# LedKeychain.net
KiCad netlist of a schematic drawn in EAGLE
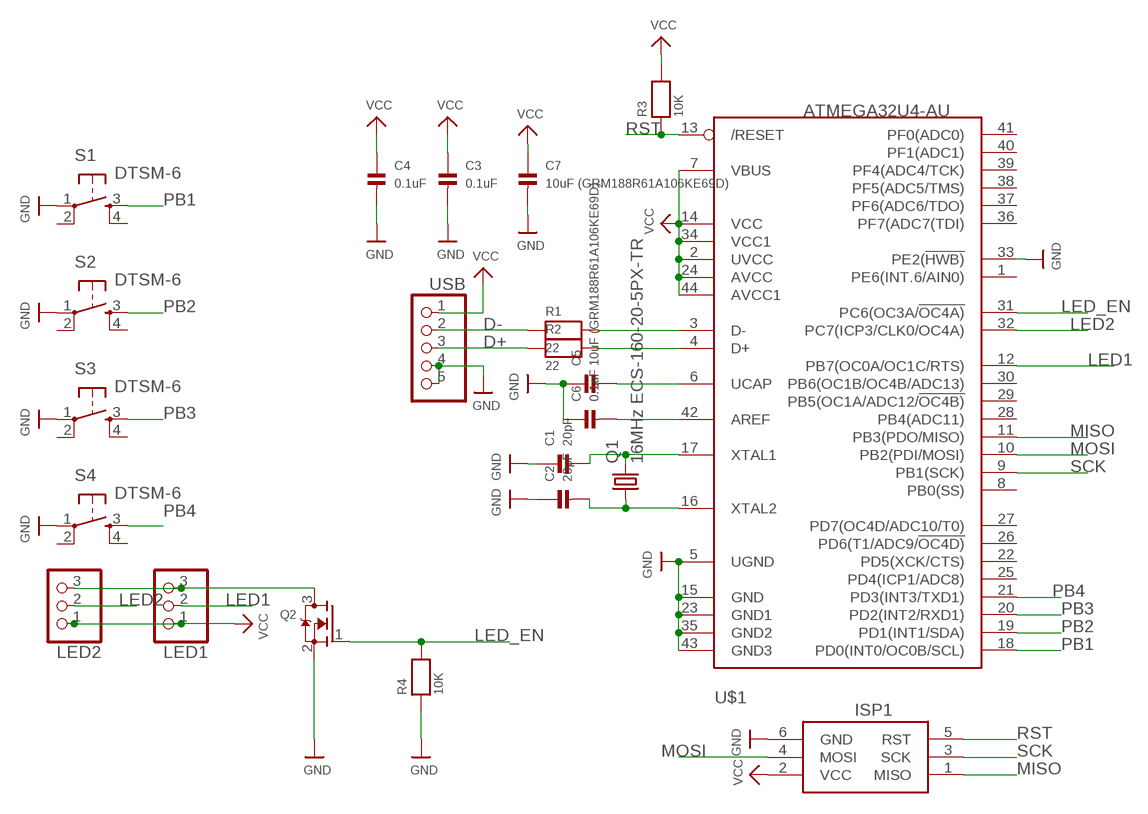
[diagram p0: schematic, sheet 1]

(export (version "E")
  (design (tool "Eeschema 10.0.6"))
  (components
    (comp (ref "C1")
      (value "20pF")
      (footprint "eagle-import:0603-MINI")
      (libsource (lib "eagle-import") (part "CAP_CERAMIC0603MINI"))
    )
    (comp (ref "C2")
      (value "20pF")
      (footprint "eagle-import:0603-MINI")
      (libsource (lib "eagle-import") (part "CAP_CERAMIC0603MINI"))
    )
    (comp (ref "C3")
      (value "0.1uF")
      (footprint "eagle-import:0603-MINI")
      (libsource (lib "eagle-import") (part "CAP_CERAMIC0603MINI"))
    )
    (comp (ref "C4")
      (value "0.1uF")
      (footprint "eagle-import:0603-MINI")
      (libsource (lib "eagle-import") (part "CAP_CERAMIC0603MINI"))
    )
    (comp (ref "C5")
      (value "10uF (GRM188R61A106KE69D)")
      (footprint "eagle-import:0603-MINI")
      (libsource (lib "eagle-import") (part "CAP_CERAMIC0603MINI"))
    )
    (comp (ref "C6")
      (value "0.1uF")
      (footprint "eagle-import:0603-MINI")
      (libsource (lib "eagle-import") (part "CAP_CERAMIC0603MINI"))
    )
    (comp (ref "C7")
      (value "10uF (GRM188R61A106KE69D)")
      (footprint "eagle-import:0603-MINI")
      (libsource (lib "eagle-import") (part "CAP_CERAMIC0603MINI"))
    )
    (comp (ref "ISP1")
      (value "AVRISP-6")
      (footprint "eagle-import:AVRISP")
      (libsource (lib "eagle-import") (part "AVRISP-6"))
    )
    (comp (ref "LED1")
      (value "PINHD-1X3")
      (footprint "eagle-import:1X03")
      (libsource (lib "eagle-import") (part "PINHD-1X3"))
    )
    (comp (ref "LED2")
      (value "PINHD-1X3")
      (footprint "eagle-import:1X03")
      (libsource (lib "eagle-import") (part "PINHD-1X3"))
    )
    (comp (ref "Q1")
      (value "16MHz ECS-160-20-5PX-TR")
      (footprint "eagle-import:HC49UP")
      (libsource (lib "eagle-import") (part "CRYSTALHC49UP"))
    )
    (comp (ref "Q2")
      (value "MOSFET-NWIDE")
      (footprint "eagle-import:SOT23-WIDE")
      (libsource (lib "eagle-import") (part "MOSFET-NWIDE"))
    )
    (comp (ref "R1")
      (value "22")
      (footprint "eagle-import:0603-MINI")
      (libsource (lib "eagle-import") (part "RESISTOR0603MINI"))
    )
    (comp (ref "R2")
      (value "22")
      (footprint "eagle-import:0603-MINI")
      (libsource (lib "eagle-import") (part "RESISTOR0603MINI"))
    )
    (comp (ref "R3")
      (value "10K")
      (footprint "eagle-import:0603-MINI")
      (libsource (lib "eagle-import") (part "RESISTOR0603MINI"))
    )
    (comp (ref "R4")
      (value "10K")
      (footprint "eagle-import:0603-MINI")
      (libsource (lib "eagle-import") (part "RESISTOR0603MINI"))
    )
    (comp (ref "S1")
      (value "DTSM-6")
      (footprint "eagle-import:DTSM-6")
      (libsource (lib "eagle-import") (part "DTSM-6"))
    )
    (comp (ref "S2")
      (value "DTSM-6")
      (footprint "eagle-import:DTSM-6")
      (libsource (lib "eagle-import") (part "DTSM-6"))
    )
    (comp (ref "S3")
      (value "DTSM-6")
      (footprint "eagle-import:DTSM-6")
      (libsource (lib "eagle-import") (part "DTSM-6"))
    )
    (comp (ref "S4")
      (value "DTSM-6")
      (footprint "eagle-import:DTSM-6")
      (libsource (lib "eagle-import") (part "DTSM-6"))
    )
    (comp (ref "U$1")
      (value "ATMEGA32U4-AU")
      (footprint "eagle-import:TQFP44")
      (libsource (lib "eagle-import") (part "ATMEGA32U4-AU"))
    )
    (comp (ref "USB")
      (value "PINHD-1X5/90")
      (footprint "eagle-import:1X05_90")
      (libsource (lib "eagle-import") (part "PINHD-1X5/90"))
    )
  )
  (nets
    (net (code "1") (name "/D+") (class "Default")
      (node (ref "R2") (pin "1") (pinfunction "1_1") (pintype "passive"))
      (node (ref "USB") (pin "3") (pinfunction "3_3") (pintype "passive"))
    )
    (net (code "2") (name "/D-") (class "Default")
      (node (ref "R1") (pin "1") (pinfunction "1_1") (pintype "passive"))
      (node (ref "USB") (pin "2") (pinfunction "2_2") (pintype "passive"))
    )
    (net (code "3") (name "/LED1") (class "Default")
      (node (ref "LED1") (pin "2") (pinfunction "2_2") (pintype "passive"))
      (node (ref "U$1") (pin "12") (pinfunction "PB7(OC0A/OC1C/RTS)_12") (pintype "bidirectional"))
    )
    (net (code "4") (name "/LED2") (class "Default")
      (node (ref "LED2") (pin "2") (pinfunction "2_2") (pintype "passive"))
      (node (ref "U$1") (pin "32") (pinfunction "PC7(ICP3/CLK0/OC4A)_32") (pintype "bidirectional"))
    )
    (net (code "5") (name "/LED_EN") (class "Default")
      (node (ref "Q2") (pin "1") (pinfunction "G_1") (pintype "bidirectional"))
      (node (ref "R4") (pin "2") (pinfunction "2_2") (pintype "passive"))
      (node (ref "U$1") (pin "31") (pinfunction "PC6(OC3A/~{OC4A})_31") (pintype "bidirectional"))
    )
    (net (code "6") (name "/MISO") (class "Default")
      (node (ref "ISP1") (pin "1") (pinfunction "MISO_1") (pintype "input"))
      (node (ref "U$1") (pin "11") (pinfunction "PB3(PDO/MISO)_11") (pintype "bidirectional"))
    )
    (net (code "7") (name "/MOSI") (class "Default")
      (node (ref "ISP1") (pin "4") (pinfunction "MOSI_4") (pintype "output"))
      (node (ref "U$1") (pin "10") (pinfunction "PB2(PDI/MOSI)_10") (pintype "bidirectional"))
    )
    (net (code "8") (name "/PB1") (class "Default")
      (node (ref "S1") (pin "3") (pinfunction "3_3") (pintype "passive"))
      (node (ref "U$1") (pin "18") (pinfunction "PD0(INT0/OC0B/SCL)_18") (pintype "bidirectional"))
    )
    (net (code "9") (name "/PB2") (class "Default")
      (node (ref "S2") (pin "3") (pinfunction "3_3") (pintype "passive"))
      (node (ref "U$1") (pin "19") (pinfunction "PD1(INT1/SDA)_19") (pintype "bidirectional"))
    )
    (net (code "10") (name "/PB3") (class "Default")
      (node (ref "S3") (pin "3") (pinfunction "3_3") (pintype "passive"))
      (node (ref "U$1") (pin "20") (pinfunction "PD2(INT2/RXD1)_20") (pintype "bidirectional"))
    )
    (net (code "11") (name "/PB4") (class "Default")
      (node (ref "S4") (pin "3") (pinfunction "3_3") (pintype "passive"))
      (node (ref "U$1") (pin "21") (pinfunction "PD3(INT3/TXD1)_21") (pintype "bidirectional"))
    )
    (net (code "12") (name "/RST") (class "Default")
      (node (ref "ISP1") (pin "5") (pinfunction "RST_5") (pintype "output"))
      (node (ref "R3") (pin "1") (pinfunction "1_1") (pintype "passive"))
      (node (ref "U$1") (pin "13") (pinfunction "/RESET_13") (pintype "bidirectional"))
    )
    (net (code "13") (name "/SCK") (class "Default")
      (node (ref "ISP1") (pin "3") (pinfunction "SCK_3") (pintype "output"))
      (node (ref "U$1") (pin "9") (pinfunction "PB1(SCK)_9") (pintype "bidirectional"))
    )
    (net (code "14") (name "GND") (class "Default")
      (node (ref "C1") (pin "1") (pinfunction "P$1_1") (pintype "passive"))
      (node (ref "C2") (pin "1") (pinfunction "P$1_1") (pintype "passive"))
      (node (ref "C3") (pin "2") (pinfunction "P$2_2") (pintype "passive"))
      (node (ref "C4") (pin "2") (pinfunction "P$2_2") (pintype "passive"))
      (node (ref "C5") (pin "1") (pinfunction "P$1_1") (pintype "passive"))
      (node (ref "C6") (pin "1") (pinfunction "P$1_1") (pintype "passive"))
      (node (ref "C7") (pin "2") (pinfunction "P$2_2") (pintype "passive"))
      (node (ref "ISP1") (pin "6") (pinfunction "GND_6") (pintype "power_in"))
      (node (ref "Q2") (pin "2") (pinfunction "S_2") (pintype "bidirectional"))
      (node (ref "R4") (pin "1") (pinfunction "1_1") (pintype "passive"))
      (node (ref "S1") (pin "1") (pinfunction "1_1") (pintype "passive"))
      (node (ref "S2") (pin "1") (pinfunction "1_1") (pintype "passive"))
      (node (ref "S3") (pin "1") (pinfunction "1_1") (pintype "passive"))
      (node (ref "S4") (pin "1") (pinfunction "1_1") (pintype "passive"))
      (node (ref "U$1") (pin "15") (pinfunction "GND_15") (pintype "bidirectional"))
      (node (ref "U$1") (pin "23") (pinfunction "GND1_23") (pintype "bidirectional"))
      (node (ref "U$1") (pin "33") (pinfunction "PE2(~{HWB})_33") (pintype "bidirectional"))
      (node (ref "U$1") (pin "35") (pinfunction "GND2_35") (pintype "bidirectional"))
      (node (ref "U$1") (pin "43") (pinfunction "GND3_43") (pintype "bidirectional"))
      (node (ref "U$1") (pin "5") (pinfunction "UGND_5") (pintype "bidirectional"))
      (node (ref "USB") (pin "4") (pinfunction "4_4") (pintype "passive"))
      (node (ref "USB") (pin "5") (pinfunction "5_5") (pintype "passive"))
    )
    (net (code "15") (name "Net-(C1-P$2)") (class "Default")
      (node (ref "C1") (pin "2") (pinfunction "P$2_2") (pintype "passive"))
      (node (ref "Q1") (pin "2") (pinfunction "2_2") (pintype "passive"))
      (node (ref "U$1") (pin "17") (pinfunction "XTAL1_17") (pintype "bidirectional"))
    )
    (net (code "16") (name "Net-(C2-P$2)") (class "Default")
      (node (ref "C2") (pin "2") (pinfunction "P$2_2") (pintype "passive"))
      (node (ref "Q1") (pin "1") (pinfunction "1_1") (pintype "passive"))
      (node (ref "U$1") (pin "16") (pinfunction "XTAL2_16") (pintype "bidirectional"))
    )
    (net (code "17") (name "Net-(C5-P$2)") (class "Default")
      (node (ref "C5") (pin "2") (pinfunction "P$2_2") (pintype "passive"))
      (node (ref "U$1") (pin "6") (pinfunction "UCAP_6") (pintype "bidirectional"))
    )
    (net (code "18") (name "Net-(C6-P$2)") (class "Default")
      (node (ref "C6") (pin "2") (pinfunction "P$2_2") (pintype "passive"))
      (node (ref "U$1") (pin "42") (pinfunction "AREF_42") (pintype "bidirectional"))
    )
    (net (code "19") (name "Net-(Q2-D)") (class "Default")
      (node (ref "LED1") (pin "3") (pinfunction "3_3") (pintype "passive"))
      (node (ref "LED2") (pin "3") (pinfunction "3_3") (pintype "passive"))
      (node (ref "Q2") (pin "3") (pinfunction "D_3") (pintype "bidirectional"))
    )
    (net (code "20") (name "Net-(U$1-D+)") (class "Default")
      (node (ref "R2") (pin "2") (pinfunction "2_2") (pintype "passive"))
      (node (ref "U$1") (pin "4") (pinfunction "D+_4") (pintype "bidirectional"))
    )
    (net (code "21") (name "Net-(U$1-D-)") (class "Default")
      (node (ref "R1") (pin "2") (pinfunction "2_2") (pintype "passive"))
      (node (ref "U$1") (pin "3") (pinfunction "D-_3") (pintype "bidirectional"))
    )
    (net (code "22") (name "VCC") (class "Default")
      (node (ref "C3") (pin "1") (pinfunction "P$1_1") (pintype "passive"))
      (node (ref "C4") (pin "1") (pinfunction "P$1_1") (pintype "passive"))
      (node (ref "C7") (pin "1") (pinfunction "P$1_1") (pintype "passive"))
      (node (ref "ISP1") (pin "2") (pinfunction "VCC_2") (pintype "power_in"))
      (node (ref "LED1") (pin "1") (pinfunction "1_1") (pintype "passive"))
      (node (ref "LED2") (pin "1") (pinfunction "1_1") (pintype "passive"))
      (node (ref "R3") (pin "2") (pinfunction "2_2") (pintype "passive"))
      (node (ref "U$1") (pin "14") (pinfunction "VCC_14") (pintype "bidirectional"))
      (node (ref "U$1") (pin "2") (pinfunction "UVCC_2") (pintype "bidirectional"))
      (node (ref "U$1") (pin "24") (pinfunction "AVCC_24") (pintype "bidirectional"))
      (node (ref "U$1") (pin "34") (pinfunction "VCC1_34") (pintype "bidirectional"))
      (node (ref "U$1") (pin "44") (pinfunction "AVCC1_44") (pintype "bidirectional"))
      (node (ref "U$1") (pin "7") (pinfunction "VBUS_7") (pintype "bidirectional"))
      (node (ref "USB") (pin "1") (pinfunction "1_1") (pintype "passive"))
    )
    (net (code "23") (name "unconnected-(S1-Pad2)") (class "Default")
      (node (ref "S1") (pin "2") (pinfunction "2_2") (pintype "passive"))
    )
    (net (code "24") (name "unconnected-(S1-Pad4)") (class "Default")
      (node (ref "S1") (pin "4") (pinfunction "4_4") (pintype "passive"))
    )
    (net (code "25") (name "unconnected-(S2-Pad2)") (class "Default")
      (node (ref "S2") (pin "2") (pinfunction "2_2") (pintype "passive"))
    )
    (net (code "26") (name "unconnected-(S2-Pad4)") (class "Default")
      (node (ref "S2") (pin "4") (pinfunction "4_4") (pintype "passive"))
    )
    (net (code "27") (name "unconnected-(S3-Pad2)") (class "Default")
      (node (ref "S3") (pin "2") (pinfunction "2_2") (pintype "passive"))
    )
    (net (code "28") (name "unconnected-(S3-Pad4)") (class "Default")
      (node (ref "S3") (pin "4") (pinfunction "4_4") (pintype "passive"))
    )
    (net (code "29") (name "unconnected-(S4-Pad2)") (class "Default")
      (node (ref "S4") (pin "2") (pinfunction "2_2") (pintype "passive"))
    )
    (net (code "30") (name "unconnected-(S4-Pad4)") (class "Default")
      (node (ref "S4") (pin "4") (pinfunction "4_4") (pintype "passive"))
    )
    (net (code "31") (name "unconnected-(U$1-PB0(SS)-Pad8)") (class "Default")
      (node (ref "U$1") (pin "8") (pinfunction "PB0(SS)_8") (pintype "bidirectional"))
    )
    (net (code "32") (name "unconnected-(U$1-PB4(ADC11)-Pad28)") (class "Default")
      (node (ref "U$1") (pin "28") (pinfunction "PB4(ADC11)_28") (pintype "bidirectional"))
    )
    (net (code "33") (name "unconnected-(U$1-PB5(OC1A{slash}ADC12{slash}~{OC4B})-Pad29)") (class "Default")
      (node (ref "U$1") (pin "29") (pinfunction "PB5(OC1A/ADC12/~{OC4B})_29") (pintype "bidirectional"))
    )
    (net (code "34") (name "unconnected-(U$1-PB6(OC1B{slash}OC4B{slash}ADC13)-Pad30)") (class "Default")
      (node (ref "U$1") (pin "30") (pinfunction "PB6(OC1B/OC4B/ADC13)_30") (pintype "bidirectional"))
    )
    (net (code "35") (name "unconnected-(U$1-PD4(ICP1{slash}ADC8)-Pad25)") (class "Default")
      (node (ref "U$1") (pin "25") (pinfunction "PD4(ICP1/ADC8)_25") (pintype "bidirectional"))
    )
    (net (code "36") (name "unconnected-(U$1-PD5(XCK{slash}CTS)-Pad22)") (class "Default")
      (node (ref "U$1") (pin "22") (pinfunction "PD5(XCK/CTS)_22") (pintype "bidirectional"))
    )
    (net (code "37") (name "unconnected-(U$1-PD6(T1{slash}ADC9{slash}~{OC4D})-Pad26)") (class "Default")
      (node (ref "U$1") (pin "26") (pinfunction "PD6(T1/ADC9/~{OC4D})_26") (pintype "bidirectional"))
    )
    (net (code "38") (name "unconnected-(U$1-PD7(OC4D{slash}ADC10{slash}T0)-Pad27)") (class "Default")
      (node (ref "U$1") (pin "27") (pinfunction "PD7(OC4D/ADC10/T0)_27") (pintype "bidirectional"))
    )
    (net (code "39") (name "unconnected-(U$1-PE6(INT.6{slash}AIN0)-Pad1)") (class "Default")
      (node (ref "U$1") (pin "1") (pinfunction "PE6(INT.6/AIN0)_1") (pintype "bidirectional"))
    )
    (net (code "40") (name "unconnected-(U$1-PF0(ADC0)-Pad41)") (class "Default")
      (node (ref "U$1") (pin "41") (pinfunction "PF0(ADC0)_41") (pintype "bidirectional"))
    )
    (net (code "41") (name "unconnected-(U$1-PF1(ADC1)-Pad40)") (class "Default")
      (node (ref "U$1") (pin "40") (pinfunction "PF1(ADC1)_40") (pintype "bidirectional"))
    )
    (net (code "42") (name "unconnected-(U$1-PF4(ADC4{slash}TCK)-Pad39)") (class "Default")
      (node (ref "U$1") (pin "39") (pinfunction "PF4(ADC4/TCK)_39") (pintype "bidirectional"))
    )
    (net (code "43") (name "unconnected-(U$1-PF5(ADC5{slash}TMS)-Pad38)") (class "Default")
      (node (ref "U$1") (pin "38") (pinfunction "PF5(ADC5/TMS)_38") (pintype "bidirectional"))
    )
    (net (code "44") (name "unconnected-(U$1-PF6(ADC6{slash}TDO)-Pad37)") (class "Default")
      (node (ref "U$1") (pin "37") (pinfunction "PF6(ADC6/TDO)_37") (pintype "bidirectional"))
    )
    (net (code "45") (name "unconnected-(U$1-PF7(ADC7(TDI)-Pad36)") (class "Default")
      (node (ref "U$1") (pin "36") (pinfunction "PF7(ADC7(TDI)_36") (pintype "bidirectional"))
    )
  )
)
